# 02_Beam_Inputs.net
KiCad netlist of a schematic drawn in Altium Designer
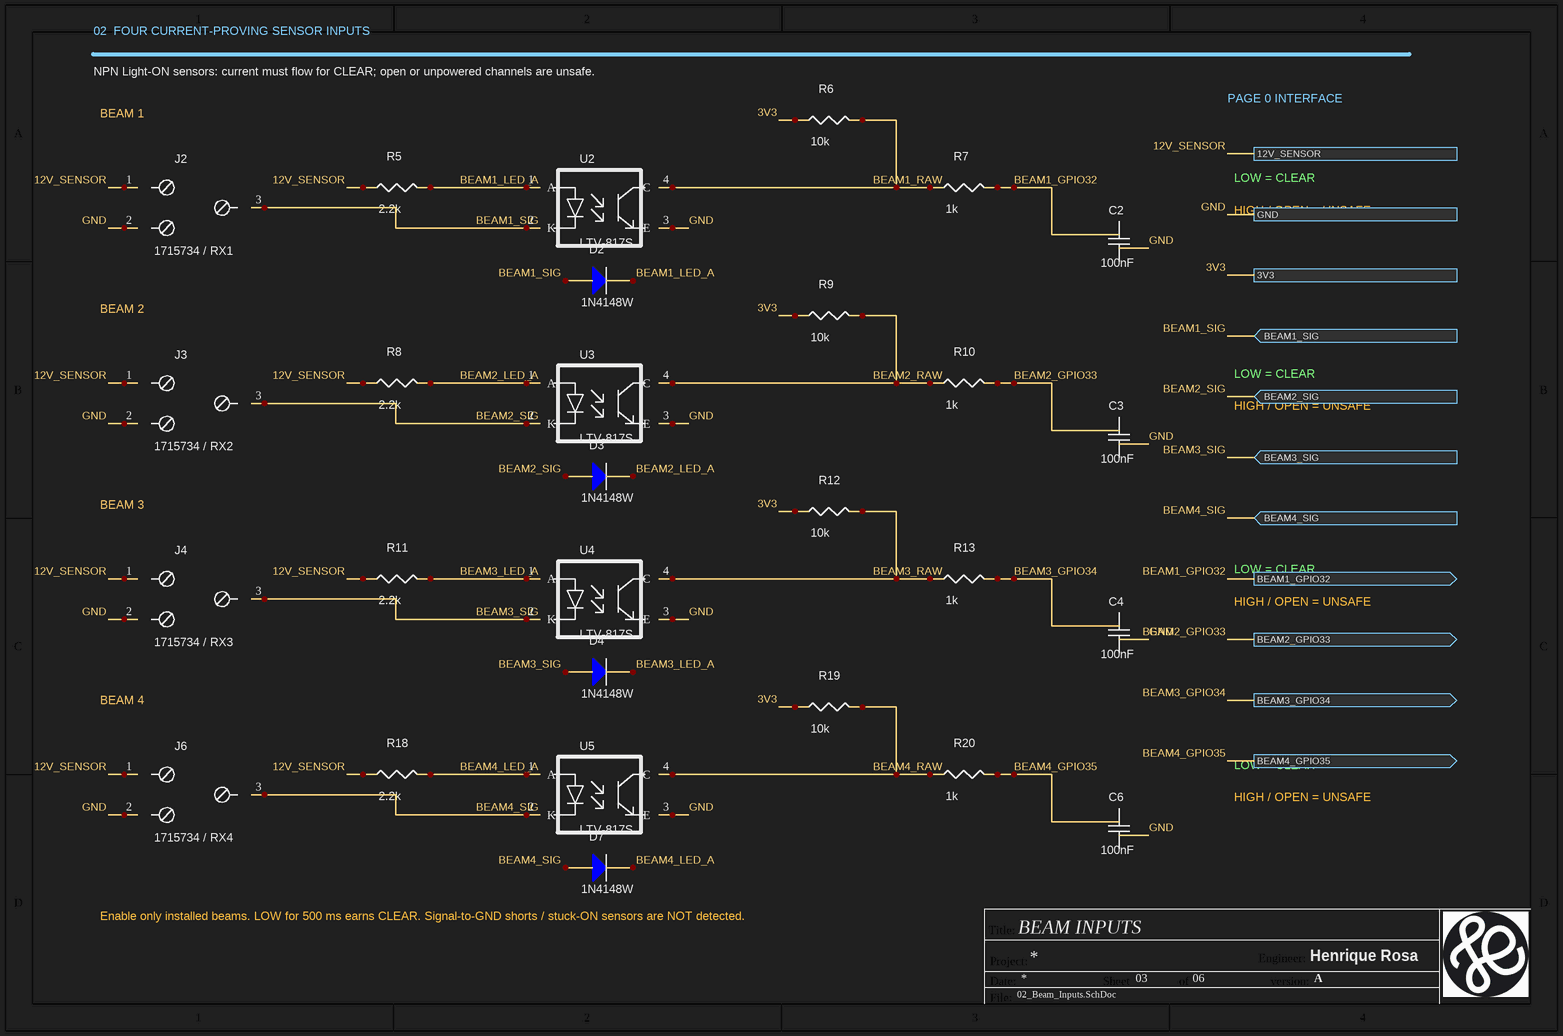
[diagram p0: 02_Beam_Inputs.SchDoc]

(export (version "E")
  (design (tool "Eeschema 10.0.6"))
  (components
    (comp (ref "C2")
      (value "100nF")
      (footprint "PCB - CAPACITOR - MLCC - MURATA GRM21B 0805_2012:MURATA GRM21B 0805_2012")
      (description "Input RC filter")
      (fields
        (field (name "MANUFACTURER") "Murata")
        (field (name "MANUFACTURER PART NUMBER") "GRM21BR71H104KA01L")
      )
      (libsource (lib "Miscellaneous Devices") (part "GRM21BR71H104KA01L"))
    )
    (comp (ref "C3")
      (value "100nF")
      (footprint "PCB - CAPACITOR - MLCC - MURATA GRM21B 0805_2012:MURATA GRM21B 0805_2012")
      (description "Input RC filter")
      (fields
        (field (name "MANUFACTURER") "Murata")
        (field (name "MANUFACTURER PART NUMBER") "GRM21BR71H104KA01L")
      )
      (libsource (lib "Miscellaneous Devices") (part "GRM21BR71H104KA01L"))
    )
    (comp (ref "C4")
      (value "100nF")
      (footprint "PCB - CAPACITOR - MLCC - MURATA GRM21B 0805_2012:MURATA GRM21B 0805_2012")
      (description "Input RC filter")
      (fields
        (field (name "MANUFACTURER") "Murata")
        (field (name "MANUFACTURER PART NUMBER") "GRM21BR71H104KA01L")
      )
      (libsource (lib "Miscellaneous Devices") (part "GRM21BR71H104KA01L"))
    )
    (comp (ref "C6")
      (value "100nF")
      (footprint "PCB - CAPACITOR - MLCC - MURATA GRM21B 0805_2012:MURATA GRM21B 0805_2012")
      (description "Input RC filter")
      (fields
        (field (name "MANUFACTURER") "Murata")
        (field (name "MANUFACTURER PART NUMBER") "GRM21BR71H104KA01L")
      )
      (libsource (lib "Miscellaneous Devices") (part "GRM21BR71H104KA01L"))
    )
    (comp (ref "D2")
      (value "1N4148W")
      (description "Reverse clamp: A to SIG; K to opto LED anode")
      (fields (field (name "PART NUMBER") "FDLL4148") (field (name "MANUFACTURER") "Nexperia"))
      (libsource (lib "Miscellaneous Devices") (part "1N4148W"))
    )
    (comp (ref "D3")
      (value "1N4148W")
      (description "Reverse clamp: A to SIG; K to opto LED anode")
      (fields (field (name "PART NUMBER") "FDLL4148") (field (name "MANUFACTURER") "Nexperia"))
      (libsource (lib "Miscellaneous Devices") (part "1N4148W"))
    )
    (comp (ref "D4")
      (value "1N4148W")
      (description "Reverse clamp: A to SIG; K to opto LED anode")
      (fields (field (name "PART NUMBER") "FDLL4148") (field (name "MANUFACTURER") "Nexperia"))
      (libsource (lib "Miscellaneous Devices") (part "1N4148W"))
    )
    (comp (ref "D7")
      (value "1N4148W")
      (description "Reverse clamp: A to SIG; K to opto LED anode")
      (fields (field (name "PART NUMBER") "FDLL4148") (field (name "MANUFACTURER") "Nexperia"))
      (libsource (lib "Miscellaneous Devices") (part "1N4148W"))
    )
    (comp (ref "J2")
      (value "1715734 / RX1")
      (footprint "OpticalHardware:PHOENIX_1715734_MKDS_3_508")
      (description "12V / GND / NPN signal terminal")
      (fields
        (field (name "MANUFACTURER") "Phoenix Contact")
        (field (name "MANUFACTURER PART NUMBER") "1715734")
      )
      (libsource (lib "PartSpecificComponents") (part "PHOENIX_1715734"))
    )
    (comp (ref "J3")
      (value "1715734 / RX2")
      (footprint "OpticalHardware:PHOENIX_1715734_MKDS_3_508")
      (description "12V / GND / NPN signal terminal")
      (fields
        (field (name "MANUFACTURER") "Phoenix Contact")
        (field (name "MANUFACTURER PART NUMBER") "1715734")
      )
      (libsource (lib "PartSpecificComponents") (part "PHOENIX_1715734"))
    )
    (comp (ref "J4")
      (value "1715734 / RX3")
      (footprint "OpticalHardware:PHOENIX_1715734_MKDS_3_508")
      (description "12V / GND / NPN signal terminal")
      (fields
        (field (name "MANUFACTURER") "Phoenix Contact")
        (field (name "MANUFACTURER PART NUMBER") "1715734")
      )
      (libsource (lib "PartSpecificComponents") (part "PHOENIX_1715734"))
    )
    (comp (ref "J6")
      (value "1715734 / RX4")
      (footprint "OpticalHardware:PHOENIX_1715734_MKDS_3_508")
      (description "12V / GND / NPN signal terminal")
      (fields
        (field (name "MANUFACTURER") "Phoenix Contact")
        (field (name "MANUFACTURER PART NUMBER") "1715734")
      )
      (libsource (lib "PartSpecificComponents") (part "PHOENIX_1715734"))
    )
    (comp (ref "R5")
      (value "2.2k")
      (footprint "PCB - RESISTOR - CHIP - YAGEO RES 0805_2012:YAGEO RES 0805_2012")
      (description "Optocoupler LED current limit")
      (fields
        (field (name "MANUFACTURER") "Yageo")
        (field (name "MANUFACTURER PART NUMBER") "RC0805FR-072K2L")
      )
      (libsource (lib "Miscellaneous Devices") (part "RC0805FR-072K2L"))
    )
    (comp (ref "R6")
      (value "10k")
      (footprint "PCB - RESISTOR - CHIP - YAGEO RES 0805_2012:YAGEO RES 0805_2012")
      (description "Pull-up earns unsafe if optocoupler is off")
      (fields
        (field (name "MANUFACTURER") "Yageo")
        (field (name "MANUFACTURER PART NUMBER") "RC0805FR-0710KL")
      )
      (libsource (lib "Miscellaneous Devices") (part "RC0805FR-0710KL"))
    )
    (comp (ref "R7")
      (value "1k")
      (footprint "PCB - RESISTOR - CHIP - YAGEO RES 0805_2012:YAGEO RES 0805_2012")
      (description "Input current limit")
      (fields
        (field (name "MANUFACTURER") "Yageo")
        (field (name "MANUFACTURER PART NUMBER") "RC0805FR-071KL")
      )
      (libsource (lib "Miscellaneous Devices") (part "RC0805FR-071KL"))
    )
    (comp (ref "R8")
      (value "2.2k")
      (footprint "PCB - RESISTOR - CHIP - YAGEO RES 0805_2012:YAGEO RES 0805_2012")
      (description "Optocoupler LED current limit")
      (fields
        (field (name "MANUFACTURER") "Yageo")
        (field (name "MANUFACTURER PART NUMBER") "RC0805FR-072K2L")
      )
      (libsource (lib "Miscellaneous Devices") (part "RC0805FR-072K2L"))
    )
    (comp (ref "R9")
      (value "10k")
      (footprint "PCB - RESISTOR - CHIP - YAGEO RES 0805_2012:YAGEO RES 0805_2012")
      (description "Pull-up earns unsafe if optocoupler is off")
      (fields
        (field (name "MANUFACTURER") "Yageo")
        (field (name "MANUFACTURER PART NUMBER") "RC0805FR-0710KL")
      )
      (libsource (lib "Miscellaneous Devices") (part "RC0805FR-0710KL"))
    )
    (comp (ref "R10")
      (value "1k")
      (footprint "PCB - RESISTOR - CHIP - YAGEO RES 0805_2012:YAGEO RES 0805_2012")
      (description "Input current limit")
      (fields
        (field (name "MANUFACTURER") "Yageo")
        (field (name "MANUFACTURER PART NUMBER") "RC0805FR-071KL")
      )
      (libsource (lib "Miscellaneous Devices") (part "RC0805FR-071KL"))
    )
    (comp (ref "R11")
      (value "2.2k")
      (footprint "PCB - RESISTOR - CHIP - YAGEO RES 0805_2012:YAGEO RES 0805_2012")
      (description "Optocoupler LED current limit")
      (fields
        (field (name "MANUFACTURER") "Yageo")
        (field (name "MANUFACTURER PART NUMBER") "RC0805FR-072K2L")
      )
      (libsource (lib "Miscellaneous Devices") (part "RC0805FR-072K2L"))
    )
    (comp (ref "R12")
      (value "10k")
      (footprint "PCB - RESISTOR - CHIP - YAGEO RES 0805_2012:YAGEO RES 0805_2012")
      (description "Pull-up earns unsafe if optocoupler is off")
      (fields
        (field (name "MANUFACTURER") "Yageo")
        (field (name "MANUFACTURER PART NUMBER") "RC0805FR-0710KL")
      )
      (libsource (lib "Miscellaneous Devices") (part "RC0805FR-0710KL"))
    )
    (comp (ref "R13")
      (value "1k")
      (footprint "PCB - RESISTOR - CHIP - YAGEO RES 0805_2012:YAGEO RES 0805_2012")
      (description "Input current limit")
      (fields
        (field (name "MANUFACTURER") "Yageo")
        (field (name "MANUFACTURER PART NUMBER") "RC0805FR-071KL")
      )
      (libsource (lib "Miscellaneous Devices") (part "RC0805FR-071KL"))
    )
    (comp (ref "R18")
      (value "2.2k")
      (footprint "PCB - RESISTOR - CHIP - YAGEO RES 0805_2012:YAGEO RES 0805_2012")
      (description "Optocoupler LED current limit")
      (fields
        (field (name "MANUFACTURER") "Yageo")
        (field (name "MANUFACTURER PART NUMBER") "RC0805FR-072K2L")
      )
      (libsource (lib "Miscellaneous Devices") (part "RC0805FR-072K2L"))
    )
    (comp (ref "R19")
      (value "10k")
      (footprint "PCB - RESISTOR - CHIP - YAGEO RES 0805_2012:YAGEO RES 0805_2012")
      (description "Pull-up earns unsafe if optocoupler is off")
      (fields
        (field (name "MANUFACTURER") "Yageo")
        (field (name "MANUFACTURER PART NUMBER") "RC0805FR-0710KL")
      )
      (libsource (lib "Miscellaneous Devices") (part "RC0805FR-0710KL"))
    )
    (comp (ref "R20")
      (value "1k")
      (footprint "PCB - RESISTOR - CHIP - YAGEO RES 0805_2012:YAGEO RES 0805_2012")
      (description "Input current limit")
      (fields
        (field (name "MANUFACTURER") "Yageo")
        (field (name "MANUFACTURER PART NUMBER") "RC0805FR-071KL")
      )
      (libsource (lib "Miscellaneous Devices") (part "RC0805FR-071KL"))
    )
    (comp (ref "U2")
      (value "LTV-817S")
      (footprint "PCB - OPTOISOLATOR - LITEON LTV-817:LITEON LTV-817")
      (description "Phototransistor optocoupler")
      (fields
        (field (name "MANUFACTURER") "Lite-On")
        (field (name "MANUFACTURER PART NUMBER") "LTV-817S-TA1")
      )
      (libsource (lib "*") (part "LTV-817S-TA1"))
    )
    (comp (ref "U3")
      (value "LTV-817S")
      (footprint "PCB - OPTOISOLATOR - LITEON LTV-817:LITEON LTV-817")
      (description "Phototransistor optocoupler")
      (fields
        (field (name "MANUFACTURER") "Lite-On")
        (field (name "MANUFACTURER PART NUMBER") "LTV-817S-TA1")
      )
      (libsource (lib "*") (part "LTV-817S-TA1"))
    )
    (comp (ref "U4")
      (value "LTV-817S")
      (footprint "PCB - OPTOISOLATOR - LITEON LTV-817:LITEON LTV-817")
      (description "Phototransistor optocoupler")
      (fields
        (field (name "MANUFACTURER") "Lite-On")
        (field (name "MANUFACTURER PART NUMBER") "LTV-817S-TA1")
      )
      (libsource (lib "*") (part "LTV-817S-TA1"))
    )
    (comp (ref "U5")
      (value "LTV-817S")
      (footprint "PCB - OPTOISOLATOR - LITEON LTV-817:LITEON LTV-817")
      (description "Phototransistor optocoupler")
      (fields
        (field (name "MANUFACTURER") "Lite-On")
        (field (name "MANUFACTURER PART NUMBER") "LTV-817S-TA1")
      )
      (libsource (lib "*") (part "LTV-817S-TA1"))
    )
  )
  (nets
    (net (code "1") (name "/3V3") (class "Default")
      (node (ref "R12") (pin "1") (pinfunction "1_1") (pintype "passive"))
      (node (ref "R19") (pin "1") (pinfunction "1_1") (pintype "passive"))
      (node (ref "R6") (pin "1") (pinfunction "1_1") (pintype "passive"))
      (node (ref "R9") (pin "1") (pinfunction "1_1") (pintype "passive"))
    )
    (net (code "2") (name "/12V_SENSOR") (class "Default")
      (node (ref "J2") (pin "1") (pinfunction "+12V_1") (pintype "passive"))
      (node (ref "J3") (pin "1") (pinfunction "+12V_1") (pintype "passive"))
      (node (ref "J4") (pin "1") (pinfunction "+12V_1") (pintype "passive"))
      (node (ref "J6") (pin "1") (pinfunction "+12V_1") (pintype "passive"))
      (node (ref "R11") (pin "1") (pinfunction "1_1") (pintype "passive"))
      (node (ref "R18") (pin "1") (pinfunction "1_1") (pintype "passive"))
      (node (ref "R5") (pin "1") (pinfunction "1_1") (pintype "passive"))
      (node (ref "R8") (pin "1") (pinfunction "1_1") (pintype "passive"))
    )
    (net (code "3") (name "/BEAM1_GPIO32") (class "Default")
      (node (ref "R7") (pin "2") (pinfunction "2_2") (pintype "passive"))
    )
    (net (code "4") (name "/BEAM1_LED_A") (class "Default")
      (node (ref "D2") (pin "2") (pinfunction "K_2") (pintype "passive"))
      (node (ref "R5") (pin "2") (pinfunction "2_2") (pintype "passive"))
      (node (ref "U2") (pin "1") (pinfunction "A_1") (pintype "passive"))
    )
    (net (code "5") (name "/BEAM1_RAW") (class "Default")
      (node (ref "R6") (pin "2") (pinfunction "2_2") (pintype "passive"))
      (node (ref "R7") (pin "1") (pinfunction "1_1") (pintype "passive"))
      (node (ref "U2") (pin "4") (pinfunction "C_4") (pintype "open_collector"))
    )
    (net (code "6") (name "/BEAM1_SIG") (class "Default")
      (node (ref "D2") (pin "1") (pinfunction "A_1") (pintype "passive"))
      (node (ref "J2") (pin "3") (pinfunction "OUT_3") (pintype "passive"))
      (node (ref "U2") (pin "2") (pinfunction "K_2") (pintype "passive"))
    )
    (net (code "7") (name "/BEAM2_GPIO33") (class "Default")
      (node (ref "R10") (pin "2") (pinfunction "2_2") (pintype "passive"))
    )
    (net (code "8") (name "/BEAM2_LED_A") (class "Default")
      (node (ref "D3") (pin "2") (pinfunction "K_2") (pintype "passive"))
      (node (ref "R8") (pin "2") (pinfunction "2_2") (pintype "passive"))
      (node (ref "U3") (pin "1") (pinfunction "A_1") (pintype "passive"))
    )
    (net (code "9") (name "/BEAM2_RAW") (class "Default")
      (node (ref "R10") (pin "1") (pinfunction "1_1") (pintype "passive"))
      (node (ref "R9") (pin "2") (pinfunction "2_2") (pintype "passive"))
      (node (ref "U3") (pin "4") (pinfunction "C_4") (pintype "open_collector"))
    )
    (net (code "10") (name "/BEAM2_SIG") (class "Default")
      (node (ref "D3") (pin "1") (pinfunction "A_1") (pintype "passive"))
      (node (ref "J3") (pin "3") (pinfunction "OUT_3") (pintype "passive"))
      (node (ref "U3") (pin "2") (pinfunction "K_2") (pintype "passive"))
    )
    (net (code "11") (name "/BEAM3_GPIO34") (class "Default")
      (node (ref "R13") (pin "2") (pinfunction "2_2") (pintype "passive"))
    )
    (net (code "12") (name "/BEAM3_LED_A") (class "Default")
      (node (ref "D4") (pin "2") (pinfunction "K_2") (pintype "passive"))
      (node (ref "R11") (pin "2") (pinfunction "2_2") (pintype "passive"))
      (node (ref "U4") (pin "1") (pinfunction "A_1") (pintype "passive"))
    )
    (net (code "13") (name "/BEAM3_RAW") (class "Default")
      (node (ref "R12") (pin "2") (pinfunction "2_2") (pintype "passive"))
      (node (ref "R13") (pin "1") (pinfunction "1_1") (pintype "passive"))
      (node (ref "U4") (pin "4") (pinfunction "C_4") (pintype "open_collector"))
    )
    (net (code "14") (name "/BEAM3_SIG") (class "Default")
      (node (ref "D4") (pin "1") (pinfunction "A_1") (pintype "passive"))
      (node (ref "J4") (pin "3") (pinfunction "OUT_3") (pintype "passive"))
      (node (ref "U4") (pin "2") (pinfunction "K_2") (pintype "passive"))
    )
    (net (code "15") (name "/BEAM4_GPIO35") (class "Default")
      (node (ref "R20") (pin "2") (pinfunction "2_2") (pintype "passive"))
    )
    (net (code "16") (name "/BEAM4_LED_A") (class "Default")
      (node (ref "D7") (pin "2") (pinfunction "K_2") (pintype "passive"))
      (node (ref "R18") (pin "2") (pinfunction "2_2") (pintype "passive"))
      (node (ref "U5") (pin "1") (pinfunction "A_1") (pintype "passive"))
    )
    (net (code "17") (name "/BEAM4_RAW") (class "Default")
      (node (ref "R19") (pin "2") (pinfunction "2_2") (pintype "passive"))
      (node (ref "R20") (pin "1") (pinfunction "1_1") (pintype "passive"))
      (node (ref "U5") (pin "4") (pinfunction "C_4") (pintype "open_collector"))
    )
    (net (code "18") (name "/BEAM4_SIG") (class "Default")
      (node (ref "D7") (pin "1") (pinfunction "A_1") (pintype "passive"))
      (node (ref "J6") (pin "3") (pinfunction "OUT_3") (pintype "passive"))
      (node (ref "U5") (pin "2") (pinfunction "K_2") (pintype "passive"))
    )
    (net (code "19") (name "/GND") (class "Default")
      (node (ref "J2") (pin "2") (pinfunction "0V_2") (pintype "passive"))
      (node (ref "J3") (pin "2") (pinfunction "0V_2") (pintype "passive"))
      (node (ref "J4") (pin "2") (pinfunction "0V_2") (pintype "passive"))
      (node (ref "J6") (pin "2") (pinfunction "0V_2") (pintype "passive"))
      (node (ref "U2") (pin "3") (pinfunction "E_3") (pintype "passive"))
      (node (ref "U3") (pin "3") (pinfunction "E_3") (pintype "passive"))
      (node (ref "U4") (pin "3") (pinfunction "E_3") (pintype "passive"))
      (node (ref "U5") (pin "3") (pinfunction "E_3") (pintype "passive"))
    )
    (net (code "20") (name "unconnected-(C2-Pad1)") (class "Default")
      (node (ref "C2") (pin "1") (pinfunction "1_1") (pintype "passive"))
    )
    (net (code "21") (name "unconnected-(C2-Pad2)") (class "Default")
      (node (ref "C2") (pin "2") (pinfunction "2_2") (pintype "passive"))
    )
    (net (code "22") (name "unconnected-(C3-Pad1)") (class "Default")
      (node (ref "C3") (pin "1") (pinfunction "1_1") (pintype "passive"))
    )
    (net (code "23") (name "unconnected-(C3-Pad2)") (class "Default")
      (node (ref "C3") (pin "2") (pinfunction "2_2") (pintype "passive"))
    )
    (net (code "24") (name "unconnected-(C4-Pad1)") (class "Default")
      (node (ref "C4") (pin "1") (pinfunction "1_1") (pintype "passive"))
    )
    (net (code "25") (name "unconnected-(C4-Pad2)") (class "Default")
      (node (ref "C4") (pin "2") (pinfunction "2_2") (pintype "passive"))
    )
    (net (code "26") (name "unconnected-(C6-Pad1)") (class "Default")
      (node (ref "C6") (pin "1") (pinfunction "1_1") (pintype "passive"))
    )
    (net (code "27") (name "unconnected-(C6-Pad2)") (class "Default")
      (node (ref "C6") (pin "2") (pinfunction "2_2") (pintype "passive"))
    )
  )
)
